# ocs-arduino-shield.net
KiCad netlist of a schematic drawn in EAGLE
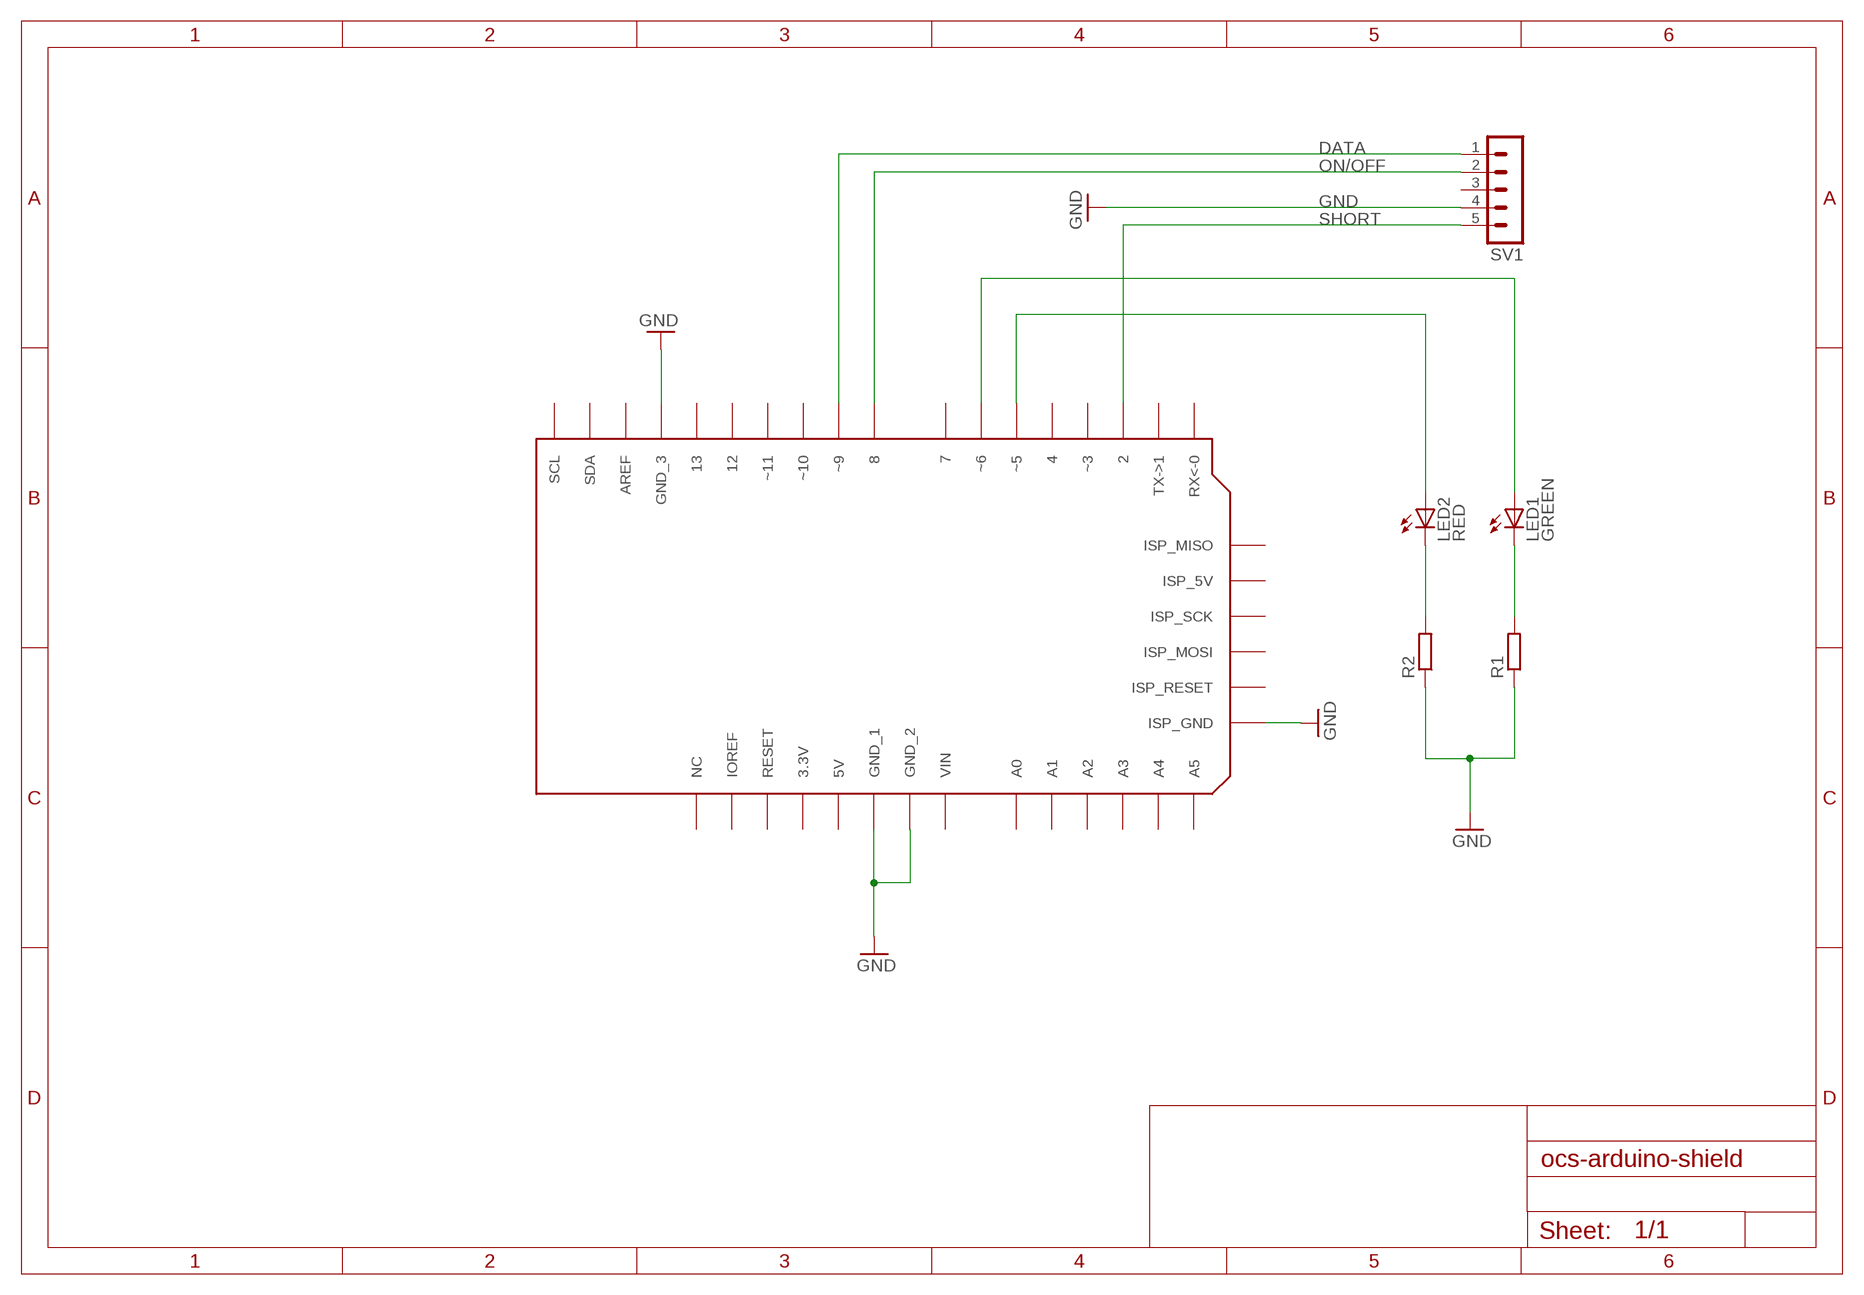
[diagram p0: schematic, sheet 1]

(export (version "E")
  (design (tool "Eeschema 10.0.6"))
  (components
    (comp (ref "LED1")
      (value "GREEN")
      (footprint "eagle-import:LED3MM")
      (libsource (lib "eagle-import") (part "LED3MM"))
    )
    (comp (ref "LED2")
      (value "RED")
      (footprint "eagle-import:LED3MM")
      (libsource (lib "eagle-import") (part "LED3MM"))
    )
    (comp (ref "R1")
      (value "R-EU_0207_10")
      (footprint "eagle-import:0207_10")
      (libsource (lib "eagle-import") (part "R-EU_0207_10"))
    )
    (comp (ref "R2")
      (value "R-EU_0207_10")
      (footprint "eagle-import:0207_10")
      (libsource (lib "eagle-import") (part "R-EU_0207_10"))
    )
    (comp (ref "SH1")
      (value "ARDUINO-UNO-SHIELD")
      (footprint "eagle-import:ARDUINO-UNO-SHIELD")
      (libsource (lib "eagle-import") (part "ARDUINO-UNO-SHIELD"))
    )
    (comp (ref "SV1")
      (value "MA05-1")
      (footprint "eagle-import:MA05-1")
      (libsource (lib "eagle-import") (part "MA05-1"))
    )
  )
  (nets
    (net (code "1") (name "/3.3V") (class "Default")
      (node (ref "SH1") (pin "3.3V") (pinfunction "3.3V_3.3V") (pintype "power_in"))
    )
    (net (code "2") (name "/5V") (class "Default")
      (node (ref "SH1") (pin "5V") (pinfunction "5V_5V") (pintype "power_in"))
    )
    (net (code "3") (name "/AREF") (class "Default")
      (node (ref "SH1") (pin "AREF") (pinfunction "AREF_AREF") (pintype "power_in"))
    )
    (net (code "4") (name "/DATA") (class "Default")
      (node (ref "SH1") (pin "~9") (pinfunction "~{9}_~9") (pintype "bidirectional"))
      (node (ref "SV1") (pin "1") (pinfunction "1_1") (pintype "passive"))
    )
    (net (code "5") (name "/ON{slash}OFF") (class "Default")
      (node (ref "SH1") (pin "8") (pinfunction "8_8") (pintype "bidirectional"))
      (node (ref "SV1") (pin "2") (pinfunction "2_2") (pintype "passive"))
    )
    (net (code "6") (name "/SHORT") (class "Default")
      (node (ref "SH1") (pin "2") (pinfunction "2_2") (pintype "bidirectional"))
      (node (ref "SV1") (pin "5") (pinfunction "5_5") (pintype "passive"))
    )
    (net (code "7") (name "/VIN") (class "Default")
      (node (ref "SH1") (pin "VIN") (pinfunction "VIN_VIN") (pintype "power_in"))
    )
    (net (code "8") (name "GND") (class "Default")
      (node (ref "R1") (pin "1") (pinfunction "1_1") (pintype "passive"))
      (node (ref "R2") (pin "1") (pinfunction "1_1") (pintype "passive"))
      (node (ref "SH1") (pin "GND_1") (pinfunction "GND_1_GND_1") (pintype "power_in"))
      (node (ref "SH1") (pin "GND_2") (pinfunction "GND_2_GND_2") (pintype "power_in"))
      (node (ref "SH1") (pin "GND_3") (pinfunction "GND_3_GND_3") (pintype "power_in"))
      (node (ref "SH1") (pin "ISP_GND") (pinfunction "ISP_GND_ISP_GND") (pintype "bidirectional"))
      (node (ref "SV1") (pin "4") (pinfunction "4_4") (pintype "passive"))
    )
    (net (code "9") (name "Net-(LED1-C)") (class "Default")
      (node (ref "LED1") (pin "K") (pinfunction "C_K") (pintype "passive"))
      (node (ref "R1") (pin "2") (pinfunction "2_2") (pintype "passive"))
    )
    (net (code "10") (name "Net-(LED2-C)") (class "Default")
      (node (ref "LED2") (pin "K") (pinfunction "C_K") (pintype "passive"))
      (node (ref "R2") (pin "2") (pinfunction "2_2") (pintype "passive"))
    )
    (net (code "11") (name "Net-(SH1-~{5})") (class "Default")
      (node (ref "LED2") (pin "A") (pinfunction "A_A") (pintype "passive"))
      (node (ref "SH1") (pin "~5") (pinfunction "~{5}_~5") (pintype "bidirectional"))
    )
    (net (code "12") (name "Net-(SH1-~{6})") (class "Default")
      (node (ref "LED1") (pin "A") (pinfunction "A_A") (pintype "passive"))
      (node (ref "SH1") (pin "~6") (pinfunction "~{6}_~6") (pintype "bidirectional"))
    )
    (net (code "13") (name "unconnected-(SH1-Pad4)") (class "Default")
      (node (ref "SH1") (pin "4") (pinfunction "4_4") (pintype "bidirectional"))
    )
    (net (code "14") (name "unconnected-(SH1-Pad7)") (class "Default")
      (node (ref "SH1") (pin "7") (pinfunction "7_7") (pintype "bidirectional"))
    )
    (net (code "15") (name "unconnected-(SH1-Pad12)") (class "Default")
      (node (ref "SH1") (pin "12") (pinfunction "12_12") (pintype "bidirectional"))
    )
    (net (code "16") (name "unconnected-(SH1-Pad13)") (class "Default")
      (node (ref "SH1") (pin "13") (pinfunction "13_13") (pintype "bidirectional"))
    )
    (net (code "17") (name "unconnected-(SH1-PadA0)") (class "Default")
      (node (ref "SH1") (pin "A0") (pinfunction "A0_A0") (pintype "bidirectional"))
    )
    (net (code "18") (name "unconnected-(SH1-PadA1)") (class "Default")
      (node (ref "SH1") (pin "A1") (pinfunction "A1_A1") (pintype "bidirectional"))
    )
    (net (code "19") (name "unconnected-(SH1-PadA2)") (class "Default")
      (node (ref "SH1") (pin "A2") (pinfunction "A2_A2") (pintype "bidirectional"))
    )
    (net (code "20") (name "unconnected-(SH1-PadA3)") (class "Default")
      (node (ref "SH1") (pin "A3") (pinfunction "A3_A3") (pintype "bidirectional"))
    )
    (net (code "21") (name "unconnected-(SH1-PadA4)") (class "Default")
      (node (ref "SH1") (pin "A4") (pinfunction "A4_A4") (pintype "bidirectional"))
    )
    (net (code "22") (name "unconnected-(SH1-PadA5)") (class "Default")
      (node (ref "SH1") (pin "A5") (pinfunction "A5_A5") (pintype "bidirectional"))
    )
    (net (code "23") (name "unconnected-(SH1-PadIOREF)") (class "Default")
      (node (ref "SH1") (pin "IOREF") (pinfunction "IOREF_IOREF") (pintype "output"))
    )
    (net (code "24") (name "unconnected-(SH1-PadISP_5V)") (class "Default")
      (node (ref "SH1") (pin "ISP_5V") (pinfunction "ISP_5V_ISP_5V") (pintype "bidirectional"))
    )
    (net (code "25") (name "unconnected-(SH1-PadISP_MISO)") (class "Default")
      (node (ref "SH1") (pin "ISP_MISO") (pinfunction "ISP_MISO_ISP_MISO") (pintype "bidirectional"))
    )
    (net (code "26") (name "unconnected-(SH1-PadISP_MOSI)") (class "Default")
      (node (ref "SH1") (pin "ISP_MOSI") (pinfunction "ISP_MOSI_ISP_MOSI") (pintype "bidirectional"))
    )
    (net (code "27") (name "unconnected-(SH1-PadISP_RESET)") (class "Default")
      (node (ref "SH1") (pin "ISP_RESET") (pinfunction "ISP_RESET_ISP_RESET") (pintype "bidirectional"))
    )
    (net (code "28") (name "unconnected-(SH1-PadISP_SCK)") (class "Default")
      (node (ref "SH1") (pin "ISP_SCK") (pinfunction "ISP_SCK_ISP_SCK") (pintype "bidirectional"))
    )
    (net (code "29") (name "unconnected-(SH1-PadNC)") (class "Default")
      (node (ref "SH1") (pin "NC") (pinfunction "NC_NC") (pintype "no_connect"))
    )
    (net (code "30") (name "unconnected-(SH1-PadRESET)") (class "Default")
      (node (ref "SH1") (pin "RESET") (pinfunction "RESET_RESET") (pintype "input"))
    )
    (net (code "31") (name "unconnected-(SH1-PadRX<-0)") (class "Default")
      (node (ref "SH1") (pin "RX<-0") (pinfunction "RX<-0_RX<-0") (pintype "input"))
    )
    (net (code "32") (name "unconnected-(SH1-PadSCL)") (class "Default")
      (node (ref "SH1") (pin "SCL") (pinfunction "SCL_SCL") (pintype "bidirectional"))
    )
    (net (code "33") (name "unconnected-(SH1-PadSDA)") (class "Default")
      (node (ref "SH1") (pin "SDA") (pinfunction "SDA_SDA") (pintype "bidirectional"))
    )
    (net (code "34") (name "unconnected-(SH1-PadTX->1)") (class "Default")
      (node (ref "SH1") (pin "TX->1") (pinfunction "TX->1_TX->1") (pintype "output"))
    )
    (net (code "35") (name "unconnected-(SH1-~{3}-Pad~3)") (class "Default")
      (node (ref "SH1") (pin "~3") (pinfunction "~{3}_~3") (pintype "bidirectional"))
    )
    (net (code "36") (name "unconnected-(SH1-~{10}-Pad~10)") (class "Default")
      (node (ref "SH1") (pin "~10") (pinfunction "~{10}_~10") (pintype "bidirectional"))
    )
    (net (code "37") (name "unconnected-(SH1-~{11}-Pad~11)") (class "Default")
      (node (ref "SH1") (pin "~11") (pinfunction "~{11}_~11") (pintype "bidirectional"))
    )
    (net (code "38") (name "unconnected-(SV1-Pad3)") (class "Default")
      (node (ref "SV1") (pin "3") (pinfunction "3_3") (pintype "passive"))
    )
  )
)
